# Sensors.net
KiCad netlist of a schematic drawn in Altium Designer
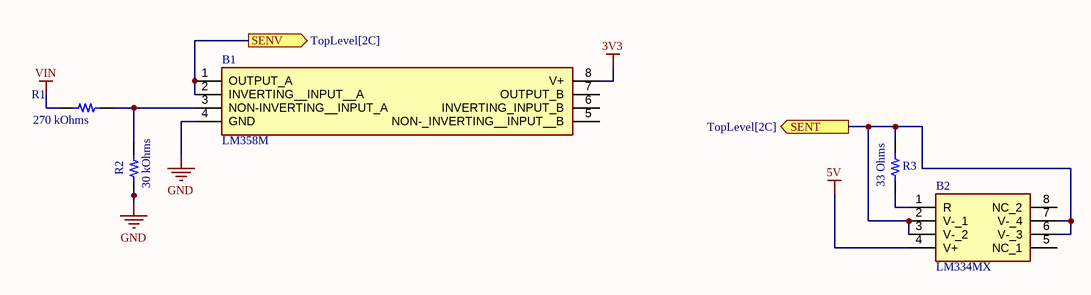
[diagram p0: Sensors.SchDoc]

(export (version "E")
  (design (tool "Eeschema 10.0.6"))
  (components
    (comp (ref "B1")
      (value "LM358M")
      (footprint "SOIC127P600X175-8N")
      (description "Low Power Dual Operational Amplifiers")
      (fields (field (name "MOUSER PART NUMBER") "926-LM358M"))
      (libsource (lib "LM358M") (part "LM358M"))
    )
    (comp (ref "B2")
      (value "LM334MX")
      (footprint "SOIC127P600X175-8N")
      (description "Current & Power Monitors & Regulators 3-Terminal Adjustable Current Source 8-SOIC 0 to 70")
      (fields (field (name "MOUSER PART NUMBER") "926-LM334MX"))
      (libsource (lib "LM334MX") (part "LM334MX"))
    )
    (comp (ref "R1")
      (value "270 kOhms")
      (footprint "YAGEO RES 0603_1608")
      (description "RES 270K OHM 1% 1/10W 0603")
      (fields (field (name "TOLERANCE") "±1%") (field (name "PART NUMBER") "RC0603FR-07270KL"))
      (libsource (lib "Celestial Altium Library - altium_library") (part "Resistor"))
    )
    (comp (ref "R2")
      (value "30 kOhms")
      (footprint "YAGEO RES 0603_1608")
      (description "RES SMD 30K OHM 1% 1/10W 0603")
      (fields (field (name "TOLERANCE") "±1%") (field (name "PART NUMBER") "AC0603FR-0730KL"))
      (libsource (lib "Celestial Altium Library - altium_library") (part "Resistor"))
    )
    (comp (ref "R3")
      (value "33 Ohms")
      (footprint "YAGEO RES 0603_1608")
      (description "RES 33 OHM 5% 1/10W 0603")
      (fields (field (name "TOLERANCE") "±5%") (field (name "PART NUMBER") "RC0603JR-0733RL"))
      (libsource (lib "Celestial Altium Library - altium_library") (part "Resistor"))
    )
  )
  (nets
    (net (code "1") (name "/SENT") (class "Default")
      (node (ref "B2") (pin "2") (pinfunction "V-_1_2") (pintype "passive"))
      (node (ref "B2") (pin "3") (pinfunction "V-_2_3") (pintype "passive"))
      (node (ref "B2") (pin "6") (pinfunction "V-_3_6") (pintype "passive"))
      (node (ref "B2") (pin "7") (pinfunction "V-_4_7") (pintype "passive"))
      (node (ref "R3") (pin "1") (pinfunction "1_1") (pintype "passive"))
    )
    (net (code "2") (name "/SENV") (class "Default")
      (node (ref "B1") (pin "1") (pinfunction "OUTPUT_A_1") (pintype "passive"))
      (node (ref "B1") (pin "2") (pinfunction "INVERTING__INPUT__A_2") (pintype "passive"))
    )
    (net (code "3") (name "3V3") (class "Default")
      (node (ref "B1") (pin "8") (pinfunction "V+_8") (pintype "passive"))
    )
    (net (code "4") (name "5V") (class "Default")
      (node (ref "B2") (pin "4") (pinfunction "V+_4") (pintype "passive"))
    )
    (net (code "5") (name "GND") (class "Default")
      (node (ref "B1") (pin "4") (pinfunction "GND_4") (pintype "passive"))
      (node (ref "R2") (pin "1") (pinfunction "1_1") (pintype "passive"))
    )
    (net (code "6") (name "Net-(B1-NON-INVERTING__INPUT_A)") (class "Default")
      (node (ref "B1") (pin "3") (pinfunction "NON-INVERTING__INPUT_A_3") (pintype "passive"))
      (node (ref "R1") (pin "1") (pinfunction "1_1") (pintype "passive"))
      (node (ref "R2") (pin "2") (pinfunction "2_2") (pintype "passive"))
    )
    (net (code "7") (name "Net-(B2-R)") (class "Default")
      (node (ref "B2") (pin "1") (pinfunction "R_1") (pintype "passive"))
      (node (ref "R3") (pin "2") (pinfunction "2_2") (pintype "passive"))
    )
    (net (code "8") (name "VIN") (class "Default")
      (node (ref "R1") (pin "2") (pinfunction "2_2") (pintype "passive"))
    )
    (net (code "9") (name "unconnected-(B1-INVERTING_INPUT_B-Pad6)") (class "Default")
      (node (ref "B1") (pin "6") (pinfunction "INVERTING_INPUT_B_6") (pintype "passive"))
    )
    (net (code "10") (name "unconnected-(B1-NON-_INVERTING__INPUT__B-Pad5)") (class "Default")
      (node (ref "B1") (pin "5") (pinfunction "NON-_INVERTING__INPUT__B_5") (pintype "passive"))
    )
    (net (code "11") (name "unconnected-(B1-OUTPUT_B-Pad7)") (class "Default")
      (node (ref "B1") (pin "7") (pinfunction "OUTPUT_B_7") (pintype "passive"))
    )
    (net (code "12") (name "unconnected-(B2-NC_1-Pad5)") (class "Default")
      (node (ref "B2") (pin "5") (pinfunction "NC_1_5") (pintype "passive"))
    )
    (net (code "13") (name "unconnected-(B2-NC_2-Pad8)") (class "Default")
      (node (ref "B2") (pin "8") (pinfunction "NC_2_8") (pintype "passive"))
    )
  )
)
